# loramesh.net
KiCad netlist of a schematic drawn in EAGLE
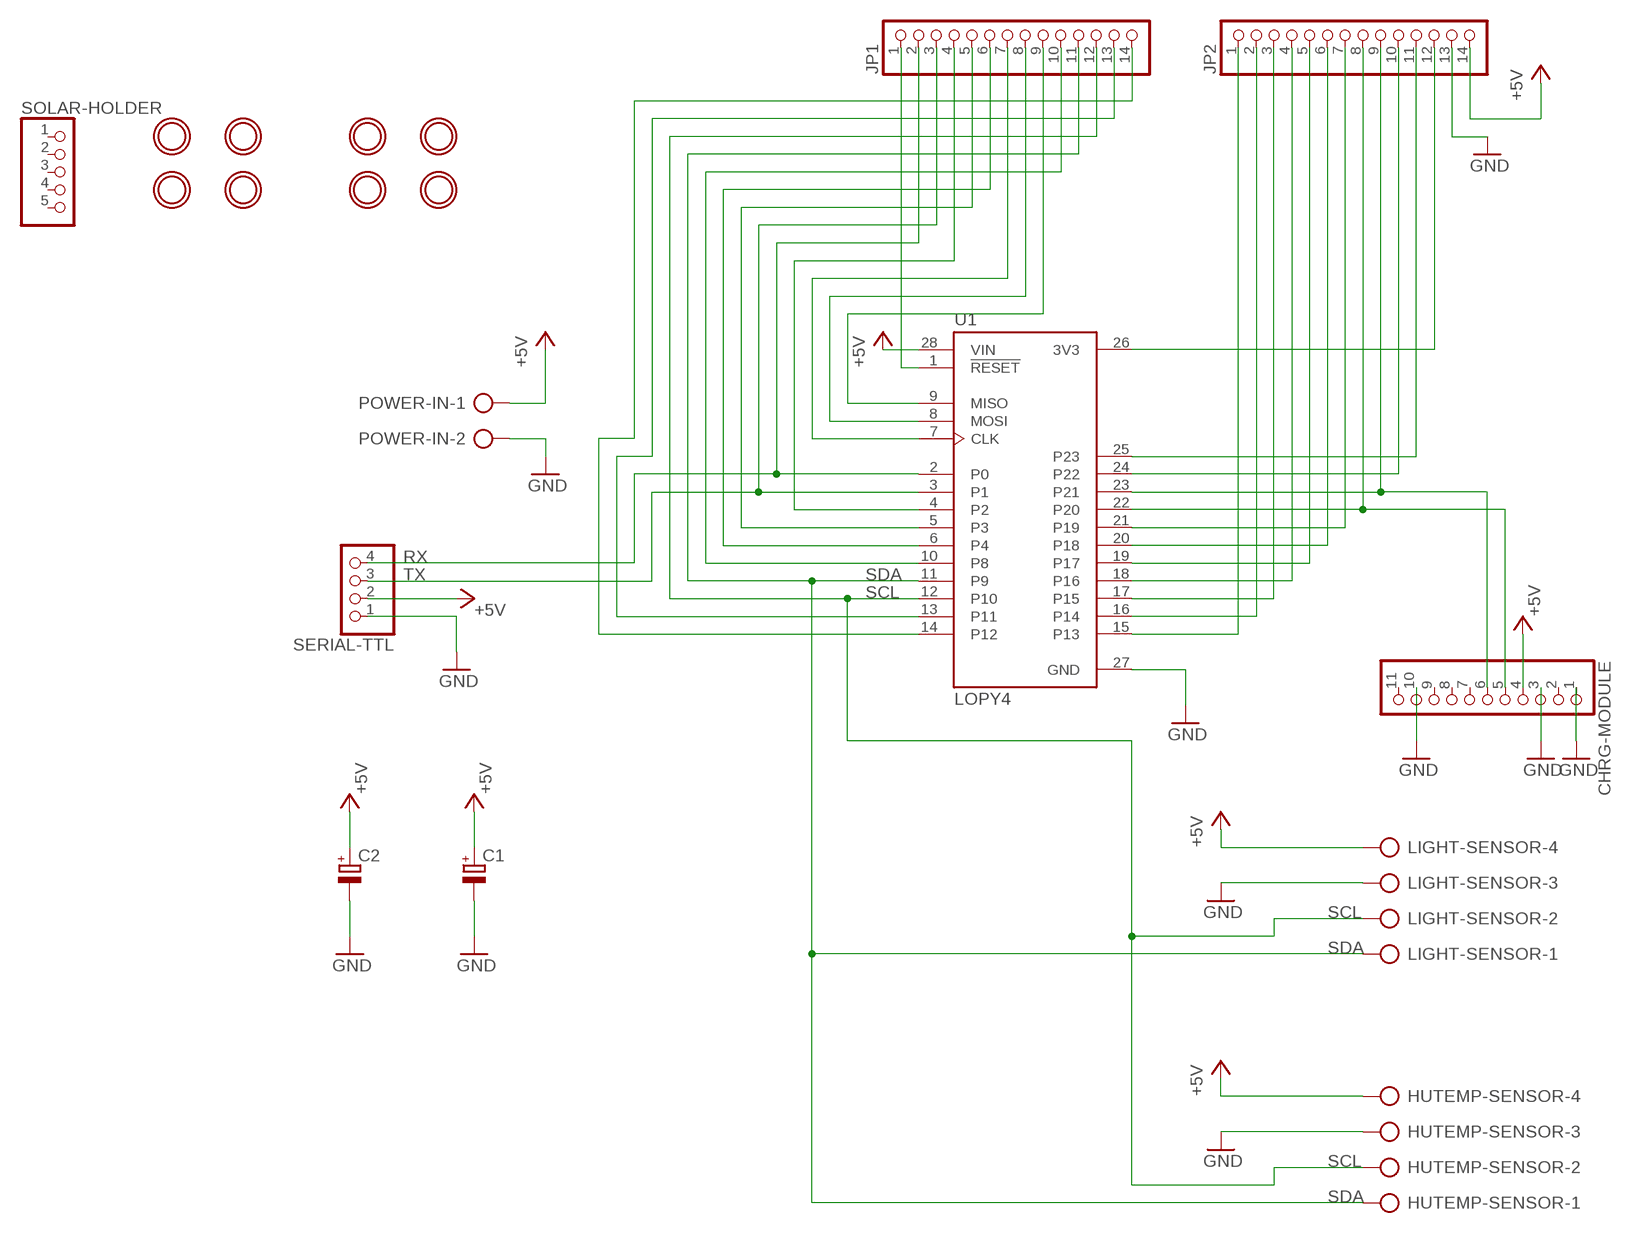
[diagram p0: schematic, sheet 1]

(export (version "E")
  (design (tool "Eeschema 10.0.6"))
  (components
    (comp (ref "C1")
      (value "CPOL-EUE2.5-5")
      (footprint "eagle-import:E2,5-5")
      (libsource (lib "eagle-import") (part "CPOL-EUE2.5-5"))
    )
    (comp (ref "C2")
      (value "CPOL-EUE2.5-5")
      (footprint "eagle-import:E2,5-5")
      (libsource (lib "eagle-import") (part "CPOL-EUE2.5-5"))
    )
    (comp (ref "CHRG-MODULE")
      (value "HEADER-1X1176MIL")
      (footprint "eagle-import:1X11_ROUND_76")
      (libsource (lib "eagle-import") (part "HEADER-1X1176MIL"))
    )
    (comp (ref "HUTEMP-SENSOR")
      (value "AK500/4")
      (footprint "eagle-import:AK500_4")
      (libsource (lib "eagle-import") (part "AK500/4"))
    )
    (comp (ref "JP1")
      (value "PINHD-1X14")
      (footprint "eagle-import:1X14")
      (libsource (lib "eagle-import") (part "PINHD-1X14"))
    )
    (comp (ref "JP2")
      (value "PINHD-1X14")
      (footprint "eagle-import:1X14")
      (libsource (lib "eagle-import") (part "PINHD-1X14"))
    )
    (comp (ref "LIGHT-SENSOR")
      (value "AK500/4")
      (footprint "eagle-import:AK500_4")
      (libsource (lib "eagle-import") (part "AK500/4"))
    )
    (comp (ref "POWER-IN")
      (value "AK500/2")
      (footprint "eagle-import:AK500_2")
      (libsource (lib "eagle-import") (part "AK500/2"))
    )
    (comp (ref "SERIAL-TTL")
      (value "PINHD-1X4")
      (footprint "eagle-import:1X04")
      (libsource (lib "eagle-import") (part "PINHD-1X4"))
    )
    (comp (ref "SOLAR-HOLDER")
      (value "PINHD-1X5")
      (footprint "eagle-import:1X05")
      (libsource (lib "eagle-import") (part "PINHD-1X5"))
    )
    (comp (ref "U$1")
      (value "MOUNTINGHOLE2.5")
      (footprint "eagle-import:MOUNTINGHOLE_2.5_PLATED")
      (libsource (lib "eagle-import") (part "MOUNTINGHOLE2.5"))
    )
    (comp (ref "U$2")
      (value "MOUNTINGHOLE2.5")
      (footprint "eagle-import:MOUNTINGHOLE_2.5_PLATED")
      (libsource (lib "eagle-import") (part "MOUNTINGHOLE2.5"))
    )
    (comp (ref "U$3")
      (value "MOUNTINGHOLE2.5")
      (footprint "eagle-import:MOUNTINGHOLE_2.5_PLATED")
      (libsource (lib "eagle-import") (part "MOUNTINGHOLE2.5"))
    )
    (comp (ref "U$4")
      (value "MOUNTINGHOLE2.5")
      (footprint "eagle-import:MOUNTINGHOLE_2.5_PLATED")
      (libsource (lib "eagle-import") (part "MOUNTINGHOLE2.5"))
    )
    (comp (ref "U$26")
      (value "MOUNTINGHOLE2.5")
      (footprint "eagle-import:MOUNTINGHOLE_2.5_PLATED")
      (libsource (lib "eagle-import") (part "MOUNTINGHOLE2.5"))
    )
    (comp (ref "U$27")
      (value "MOUNTINGHOLE2.5")
      (footprint "eagle-import:MOUNTINGHOLE_2.5_PLATED")
      (libsource (lib "eagle-import") (part "MOUNTINGHOLE2.5"))
    )
    (comp (ref "U$28")
      (value "MOUNTINGHOLE2.5")
      (footprint "eagle-import:MOUNTINGHOLE_2.5_PLATED")
      (libsource (lib "eagle-import") (part "MOUNTINGHOLE2.5"))
    )
    (comp (ref "U$29")
      (value "MOUNTINGHOLE2.5")
      (footprint "eagle-import:MOUNTINGHOLE_2.5_PLATED")
      (libsource (lib "eagle-import") (part "MOUNTINGHOLE2.5"))
    )
    (comp (ref "U1")
      (value "LOPY4")
      (footprint "eagle-import:MODULE_LOPY4")
      (fields (field (name "MF") "Pycom Ltd."))
      (libsource (lib "eagle-import") (part "LOPY4"))
    )
  )
  (nets
    (net (code "1") (name "+5V") (class "Default")
      (node (ref "C1") (pin "+") (pinfunction "+_+") (pintype "passive"))
      (node (ref "C2") (pin "+") (pinfunction "+_+") (pintype "passive"))
      (node (ref "CHRG-MODULE") (pin "4") (pinfunction "4_4") (pintype "passive"))
      (node (ref "HUTEMP-SENSOR") (pin "4") (pinfunction "KL_4") (pintype "passive"))
      (node (ref "JP2") (pin "14") (pinfunction "14_14") (pintype "passive"))
      (node (ref "LIGHT-SENSOR") (pin "4") (pinfunction "KL_4") (pintype "passive"))
      (node (ref "POWER-IN") (pin "1") (pinfunction "KL_1") (pintype "passive"))
      (node (ref "SERIAL-TTL") (pin "2") (pinfunction "2_2") (pintype "passive"))
      (node (ref "U1") (pin "28") (pinfunction "VIN_28") (pintype "input"))
    )
    (net (code "2") (name "/RX") (class "Default")
      (node (ref "JP1") (pin "2") (pinfunction "2_2") (pintype "passive"))
      (node (ref "SERIAL-TTL") (pin "4") (pinfunction "4_4") (pintype "passive"))
      (node (ref "U1") (pin "2") (pinfunction "P0_2") (pintype "bidirectional"))
    )
    (net (code "3") (name "/SCL") (class "Default")
      (node (ref "HUTEMP-SENSOR") (pin "2") (pinfunction "KL_2") (pintype "passive"))
      (node (ref "JP1") (pin "12") (pinfunction "12_12") (pintype "passive"))
      (node (ref "LIGHT-SENSOR") (pin "2") (pinfunction "KL_2") (pintype "passive"))
      (node (ref "U1") (pin "12") (pinfunction "P10_12") (pintype "bidirectional"))
    )
    (net (code "4") (name "/SDA") (class "Default")
      (node (ref "HUTEMP-SENSOR") (pin "1") (pinfunction "KL_1") (pintype "passive"))
      (node (ref "JP1") (pin "11") (pinfunction "11_11") (pintype "passive"))
      (node (ref "LIGHT-SENSOR") (pin "1") (pinfunction "KL_1") (pintype "passive"))
      (node (ref "U1") (pin "11") (pinfunction "P9_11") (pintype "bidirectional"))
    )
    (net (code "5") (name "/TX") (class "Default")
      (node (ref "JP1") (pin "3") (pinfunction "3_3") (pintype "passive"))
      (node (ref "SERIAL-TTL") (pin "3") (pinfunction "3_3") (pintype "passive"))
      (node (ref "U1") (pin "3") (pinfunction "P1_3") (pintype "bidirectional"))
    )
    (net (code "6") (name "GND") (class "Default")
      (node (ref "C1") (pin "-") (pinfunction "-_-") (pintype "passive"))
      (node (ref "C2") (pin "-") (pinfunction "-_-") (pintype "passive"))
      (node (ref "CHRG-MODULE") (pin "1") (pinfunction "1_1") (pintype "passive"))
      (node (ref "CHRG-MODULE") (pin "10") (pinfunction "10_10") (pintype "passive"))
      (node (ref "CHRG-MODULE") (pin "3") (pinfunction "3_3") (pintype "passive"))
      (node (ref "HUTEMP-SENSOR") (pin "3") (pinfunction "KL_3") (pintype "passive"))
      (node (ref "JP2") (pin "13") (pinfunction "13_13") (pintype "passive"))
      (node (ref "LIGHT-SENSOR") (pin "3") (pinfunction "KL_3") (pintype "passive"))
      (node (ref "POWER-IN") (pin "2") (pinfunction "KL_2") (pintype "passive"))
      (node (ref "SERIAL-TTL") (pin "1") (pinfunction "1_1") (pintype "passive"))
      (node (ref "U1") (pin "27") (pinfunction "GND_27") (pintype "power_in"))
    )
    (net (code "7") (name "Net-(U1-3V3)") (class "Default")
      (node (ref "JP2") (pin "12") (pinfunction "12_12") (pintype "passive"))
      (node (ref "U1") (pin "26") (pinfunction "3V3_26") (pintype "output"))
    )
    (net (code "8") (name "Net-(U1-CLK)") (class "Default")
      (node (ref "JP1") (pin "7") (pinfunction "7_7") (pintype "passive"))
      (node (ref "U1") (pin "7") (pinfunction "CLK_7") (pintype "output"))
    )
    (net (code "9") (name "Net-(U1-MISO)") (class "Default")
      (node (ref "JP1") (pin "9") (pinfunction "9_9") (pintype "passive"))
      (node (ref "U1") (pin "9") (pinfunction "MISO_9") (pintype "input"))
    )
    (net (code "10") (name "Net-(U1-MOSI)") (class "Default")
      (node (ref "JP1") (pin "8") (pinfunction "8_8") (pintype "passive"))
      (node (ref "U1") (pin "8") (pinfunction "MOSI_8") (pintype "output"))
    )
    (net (code "11") (name "Net-(U1-P2)") (class "Default")
      (node (ref "JP1") (pin "4") (pinfunction "4_4") (pintype "passive"))
      (node (ref "U1") (pin "4") (pinfunction "P2_4") (pintype "bidirectional"))
    )
    (net (code "12") (name "Net-(U1-P3)") (class "Default")
      (node (ref "JP1") (pin "5") (pinfunction "5_5") (pintype "passive"))
      (node (ref "U1") (pin "5") (pinfunction "P3_5") (pintype "bidirectional"))
    )
    (net (code "13") (name "Net-(U1-P4)") (class "Default")
      (node (ref "JP1") (pin "6") (pinfunction "6_6") (pintype "passive"))
      (node (ref "U1") (pin "6") (pinfunction "P4_6") (pintype "bidirectional"))
    )
    (net (code "14") (name "Net-(U1-P8)") (class "Default")
      (node (ref "JP1") (pin "10") (pinfunction "10_10") (pintype "passive"))
      (node (ref "U1") (pin "10") (pinfunction "P8_10") (pintype "bidirectional"))
    )
    (net (code "15") (name "Net-(U1-P11)") (class "Default")
      (node (ref "JP1") (pin "13") (pinfunction "13_13") (pintype "passive"))
      (node (ref "U1") (pin "13") (pinfunction "P11_13") (pintype "bidirectional"))
    )
    (net (code "16") (name "Net-(U1-P12)") (class "Default")
      (node (ref "JP1") (pin "14") (pinfunction "14_14") (pintype "passive"))
      (node (ref "U1") (pin "14") (pinfunction "P12_14") (pintype "bidirectional"))
    )
    (net (code "17") (name "Net-(U1-P13)") (class "Default")
      (node (ref "JP2") (pin "1") (pinfunction "1_1") (pintype "passive"))
      (node (ref "U1") (pin "15") (pinfunction "P13_15") (pintype "input"))
    )
    (net (code "18") (name "Net-(U1-P14)") (class "Default")
      (node (ref "JP2") (pin "2") (pinfunction "2_2") (pintype "passive"))
      (node (ref "U1") (pin "16") (pinfunction "P14_16") (pintype "input"))
    )
    (net (code "19") (name "Net-(U1-P15)") (class "Default")
      (node (ref "JP2") (pin "3") (pinfunction "3_3") (pintype "passive"))
      (node (ref "U1") (pin "17") (pinfunction "P15_17") (pintype "input"))
    )
    (net (code "20") (name "Net-(U1-P16)") (class "Default")
      (node (ref "JP2") (pin "4") (pinfunction "4_4") (pintype "passive"))
      (node (ref "U1") (pin "18") (pinfunction "P16_18") (pintype "input"))
    )
    (net (code "21") (name "Net-(U1-P17)") (class "Default")
      (node (ref "JP2") (pin "5") (pinfunction "5_5") (pintype "passive"))
      (node (ref "U1") (pin "19") (pinfunction "P17_19") (pintype "input"))
    )
    (net (code "22") (name "Net-(U1-P18)") (class "Default")
      (node (ref "JP2") (pin "6") (pinfunction "6_6") (pintype "passive"))
      (node (ref "U1") (pin "20") (pinfunction "P18_20") (pintype "input"))
    )
    (net (code "23") (name "Net-(U1-P19)") (class "Default")
      (node (ref "JP2") (pin "7") (pinfunction "7_7") (pintype "passive"))
      (node (ref "U1") (pin "21") (pinfunction "P19_21") (pintype "bidirectional"))
    )
    (net (code "24") (name "Net-(U1-P20)") (class "Default")
      (node (ref "CHRG-MODULE") (pin "5") (pinfunction "5_5") (pintype "passive"))
      (node (ref "JP2") (pin "8") (pinfunction "8_8") (pintype "passive"))
      (node (ref "U1") (pin "22") (pinfunction "P20_22") (pintype "bidirectional"))
    )
    (net (code "25") (name "Net-(U1-P21)") (class "Default")
      (node (ref "CHRG-MODULE") (pin "6") (pinfunction "6_6") (pintype "passive"))
      (node (ref "JP2") (pin "9") (pinfunction "9_9") (pintype "passive"))
      (node (ref "U1") (pin "23") (pinfunction "P21_23") (pintype "bidirectional"))
    )
    (net (code "26") (name "Net-(U1-P22)") (class "Default")
      (node (ref "JP2") (pin "10") (pinfunction "10_10") (pintype "passive"))
      (node (ref "U1") (pin "24") (pinfunction "P22_24") (pintype "bidirectional"))
    )
    (net (code "27") (name "Net-(U1-P23)") (class "Default")
      (node (ref "JP2") (pin "11") (pinfunction "11_11") (pintype "passive"))
      (node (ref "U1") (pin "25") (pinfunction "P23_25") (pintype "bidirectional"))
    )
    (net (code "28") (name "Net-(U1-~{RESET})") (class "Default")
      (node (ref "JP1") (pin "1") (pinfunction "1_1") (pintype "passive"))
      (node (ref "U1") (pin "1") (pinfunction "~{RESET}_1") (pintype "input"))
    )
    (net (code "29") (name "unconnected-(CHRG-MODULE-Pad2)") (class "Default")
      (node (ref "CHRG-MODULE") (pin "2") (pinfunction "2_2") (pintype "passive"))
    )
    (net (code "30") (name "unconnected-(CHRG-MODULE-Pad7)") (class "Default")
      (node (ref "CHRG-MODULE") (pin "7") (pinfunction "7_7") (pintype "passive"))
    )
    (net (code "31") (name "unconnected-(CHRG-MODULE-Pad8)") (class "Default")
      (node (ref "CHRG-MODULE") (pin "8") (pinfunction "8_8") (pintype "passive"))
    )
    (net (code "32") (name "unconnected-(CHRG-MODULE-Pad9)") (class "Default")
      (node (ref "CHRG-MODULE") (pin "9") (pinfunction "9_9") (pintype "passive"))
    )
    (net (code "33") (name "unconnected-(CHRG-MODULE-Pad11)") (class "Default")
      (node (ref "CHRG-MODULE") (pin "11") (pinfunction "11_11") (pintype "passive"))
    )
    (net (code "34") (name "unconnected-(SOLAR-HOLDER-Pad1)") (class "Default")
      (node (ref "SOLAR-HOLDER") (pin "1") (pinfunction "1_1") (pintype "passive"))
    )
    (net (code "35") (name "unconnected-(SOLAR-HOLDER-Pad2)") (class "Default")
      (node (ref "SOLAR-HOLDER") (pin "2") (pinfunction "2_2") (pintype "passive"))
    )
    (net (code "36") (name "unconnected-(SOLAR-HOLDER-Pad3)") (class "Default")
      (node (ref "SOLAR-HOLDER") (pin "3") (pinfunction "3_3") (pintype "passive"))
    )
    (net (code "37") (name "unconnected-(SOLAR-HOLDER-Pad4)") (class "Default")
      (node (ref "SOLAR-HOLDER") (pin "4") (pinfunction "4_4") (pintype "passive"))
    )
    (net (code "38") (name "unconnected-(SOLAR-HOLDER-Pad5)") (class "Default")
      (node (ref "SOLAR-HOLDER") (pin "5") (pinfunction "5_5") (pintype "passive"))
    )
  )
)
